# EPS_Distribution_LCL-FPF.net
KiCad netlist of a schematic drawn in Altium Designer
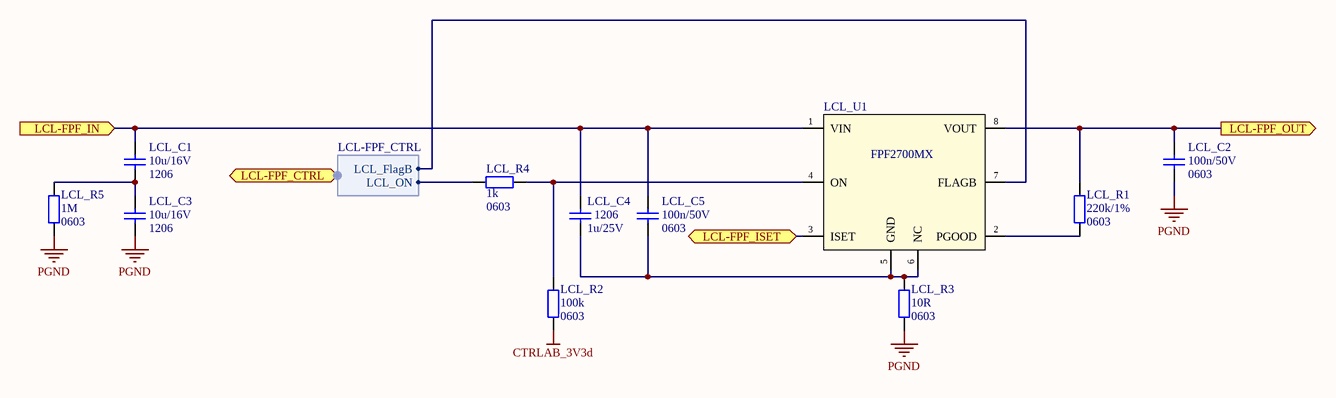
[diagram p0: EPS_Distribution_LCL-FPF.SchDoc]

(export (version "E")
  (design (tool "Eeschema 10.0.6"))
  (components
    (comp (ref "LCL_C1")
      (value "10u/16V")
      (footprint "SMD_Capacitor_1206")
      (description "Ceramic Cap Kemet COTS 10u/16V X7R 1206")
      (fields
        (field (name "MANUFACTURERPARTNUMBER") "C1206T106K4RACTU")
        (field (name "MANUFACTURER") "Kemet")
        (field (name "PACKGE") "1206")
      )
      (libsource (lib "capacitors") (part "Cer_C1206T106K4RACTU"))
    )
    (comp (ref "LCL_C2")
      (value "100n/50V")
      (footprint "SMD_Capacitor_0603")
      (description "Ceramic Cap Kemet COTS 100n/50V X7R 0603")
      (fields
        (field (name "MANUFACTURER") "Kemet")
        (field (name "MANUFACTURERPARTNUMBER") "C0603T104K5RALTU")
        (field (name "PACKAGE") "0603")
      )
      (libsource (lib "capacitors") (part "Cer_C0603T104K5RALTU"))
    )
    (comp (ref "LCL_C3")
      (value "10u/16V")
      (footprint "SMD_Capacitor_1206")
      (description "Ceramic Cap Kemet COTS 10u/16V X7R 1206")
      (fields
        (field (name "MANUFACTURERPARTNUMBER") "C1206T106K4RACTU")
        (field (name "MANUFACTURER") "Kemet")
        (field (name "PACKGE") "1206")
      )
      (libsource (lib "capacitors") (part "Cer_C1206T106K4RACTU"))
    )
    (comp (ref "LCL_C4")
      (value "1u/25V")
      (footprint "SMD_Capacitor_1206")
      (description "Ceramic Cap Kemet COTS 1u/25V X7R 1206")
      (fields
        (field (name "MANUFACTURERPARTNUMBER") "C1206T105K3RALTU")
        (field (name "MANUFACTURER") "Kemet")
        (field (name "PACKAGE") "1206")
      )
      (libsource (lib "capacitors") (part "Cer_C1206T105K3RALTU"))
    )
    (comp (ref "LCL_C5")
      (value "100n/50V")
      (footprint "SMD_Capacitor_0603")
      (description "Ceramic Cap Kemet COTS 100n/50V X7R 0603")
      (fields
        (field (name "MANUFACTURER") "Kemet")
        (field (name "MANUFACTURERPARTNUMBER") "C0603T104K5RALTU")
        (field (name "PACKAGE") "0603")
      )
      (libsource (lib "capacitors") (part "Cer_C0603T104K5RALTU"))
    )
    (comp (ref "LCL_R1")
      (value "220k/1%")
      (footprint "SMD_Resistor_0603")
      (fields (field (name "PACKAGE") "0603"))
      (libsource (lib "resistors") (part "Res"))
    )
    (comp (ref "LCL_R2")
      (value "100k")
      (footprint "SMD_Resistor_0603")
      (fields (field (name "PACKAGE") "0603"))
      (libsource (lib "resistors") (part "Res"))
    )
    (comp (ref "LCL_R3")
      (value "10R")
      (footprint "SMD_Resistor_0603")
      (fields (field (name "PACKAGE") "0603"))
      (libsource (lib "resistors") (part "Res"))
    )
    (comp (ref "LCL_R4")
      (value "1k")
      (footprint "SMD_Resistor_0603")
      (fields (field (name "PACKAGE") "0603"))
      (libsource (lib "") (part "Res_1"))
    )
    (comp (ref "LCL_R5")
      (value "1M")
      (footprint "SMD_Resistor_0603")
      (fields (field (name "PACKAGE") "0603"))
      (libsource (lib "resistors") (part "Res"))
    )
    (comp (ref "LCL_U1")
      (value "FPF2700MX")
      (footprint "SOIC-8-N")
      (description "Adj over-current protection 0.4-2A, Load Switch")
      (fields (field (name "MANUFACTURER") "Fairchild Semiconductor"))
      (libsource (lib "microcircuits") (part "FPF2700MX"))
    )
  )
  (nets
    (net (code "2") (name "/LCL-FPF_IN") (class "Default")
      (node (ref "LCL_C1") (pin "1") (pinfunction "1_1") (pintype "passive"))
      (node (ref "LCL_C4") (pin "1") (pinfunction "1_1") (pintype "passive"))
      (node (ref "LCL_C5") (pin "1") (pinfunction "1_1") (pintype "passive"))
      (node (ref "LCL_U1") (pin "1") (pinfunction "VIN_1") (pintype "passive"))
    )
    (net (code "3") (name "/LCL-FPF_ISET") (class "Default")
      (node (ref "LCL_U1") (pin "3") (pinfunction "ISET_3") (pintype "passive"))
    )
    (net (code "4") (name "/LCL-FPF_OUT") (class "Default")
      (node (ref "LCL_C2") (pin "1") (pinfunction "1_1") (pintype "passive"))
      (node (ref "LCL_R1") (pin "2") (pinfunction "2_2") (pintype "passive"))
      (node (ref "LCL_U1") (pin "8") (pinfunction "VOUT_8") (pintype "passive"))
    )
    (net (code "5") (name "/LCL_FlagB") (class "Default")
      (node (ref "LCL_U1") (pin "7") (pinfunction "FLAGB_7") (pintype "passive"))
    )
    (net (code "6") (name "/LCL_ON") (class "Default")
      (node (ref "LCL_R4") (pin "2") (pinfunction "2_2") (pintype "passive"))
    )
    (net (code "8") (name "CTRLAB_3V3d") (class "Default")
      (node (ref "LCL_R2") (pin "1") (pinfunction "1_1") (pintype "passive"))
    )
    (net (code "9") (name "Net-(LCL_C1-Pad2)") (class "Default")
      (node (ref "LCL_C1") (pin "2") (pinfunction "2_2") (pintype "passive"))
      (node (ref "LCL_C3") (pin "1") (pinfunction "1_1") (pintype "passive"))
      (node (ref "LCL_R5") (pin "2") (pinfunction "2_2") (pintype "passive"))
    )
    (net (code "10") (name "Net-(LCL_U1-GND)") (class "Default")
      (node (ref "LCL_C4") (pin "2") (pinfunction "2_2") (pintype "passive"))
      (node (ref "LCL_C5") (pin "2") (pinfunction "2_2") (pintype "passive"))
      (node (ref "LCL_R3") (pin "2") (pinfunction "2_2") (pintype "passive"))
      (node (ref "LCL_U1") (pin "5") (pinfunction "GND_5") (pintype "passive"))
      (node (ref "LCL_U1") (pin "6") (pinfunction "NC_6") (pintype "passive"))
    )
    (net (code "11") (name "Net-(LCL_U1-ON)") (class "Default")
      (node (ref "LCL_R2") (pin "2") (pinfunction "2_2") (pintype "passive"))
      (node (ref "LCL_R4") (pin "1") (pinfunction "1_1") (pintype "passive"))
      (node (ref "LCL_U1") (pin "4") (pinfunction "ON_4") (pintype "passive"))
    )
    (net (code "12") (name "Net-(LCL_U1-PGOOD)") (class "Default")
      (node (ref "LCL_R1") (pin "1") (pinfunction "1_1") (pintype "passive"))
      (node (ref "LCL_U1") (pin "2") (pinfunction "PGOOD_2") (pintype "passive"))
    )
    (net (code "13") (name "PGND") (class "Default")
      (node (ref "LCL_C2") (pin "2") (pinfunction "2_2") (pintype "passive"))
      (node (ref "LCL_C3") (pin "2") (pinfunction "2_2") (pintype "passive"))
      (node (ref "LCL_R3") (pin "1") (pinfunction "1_1") (pintype "passive"))
      (node (ref "LCL_R5") (pin "1") (pinfunction "1_1") (pintype "passive"))
    )
  )
)
